# STM32F030.net
KiCad netlist of a schematic drawn in Altium Designer
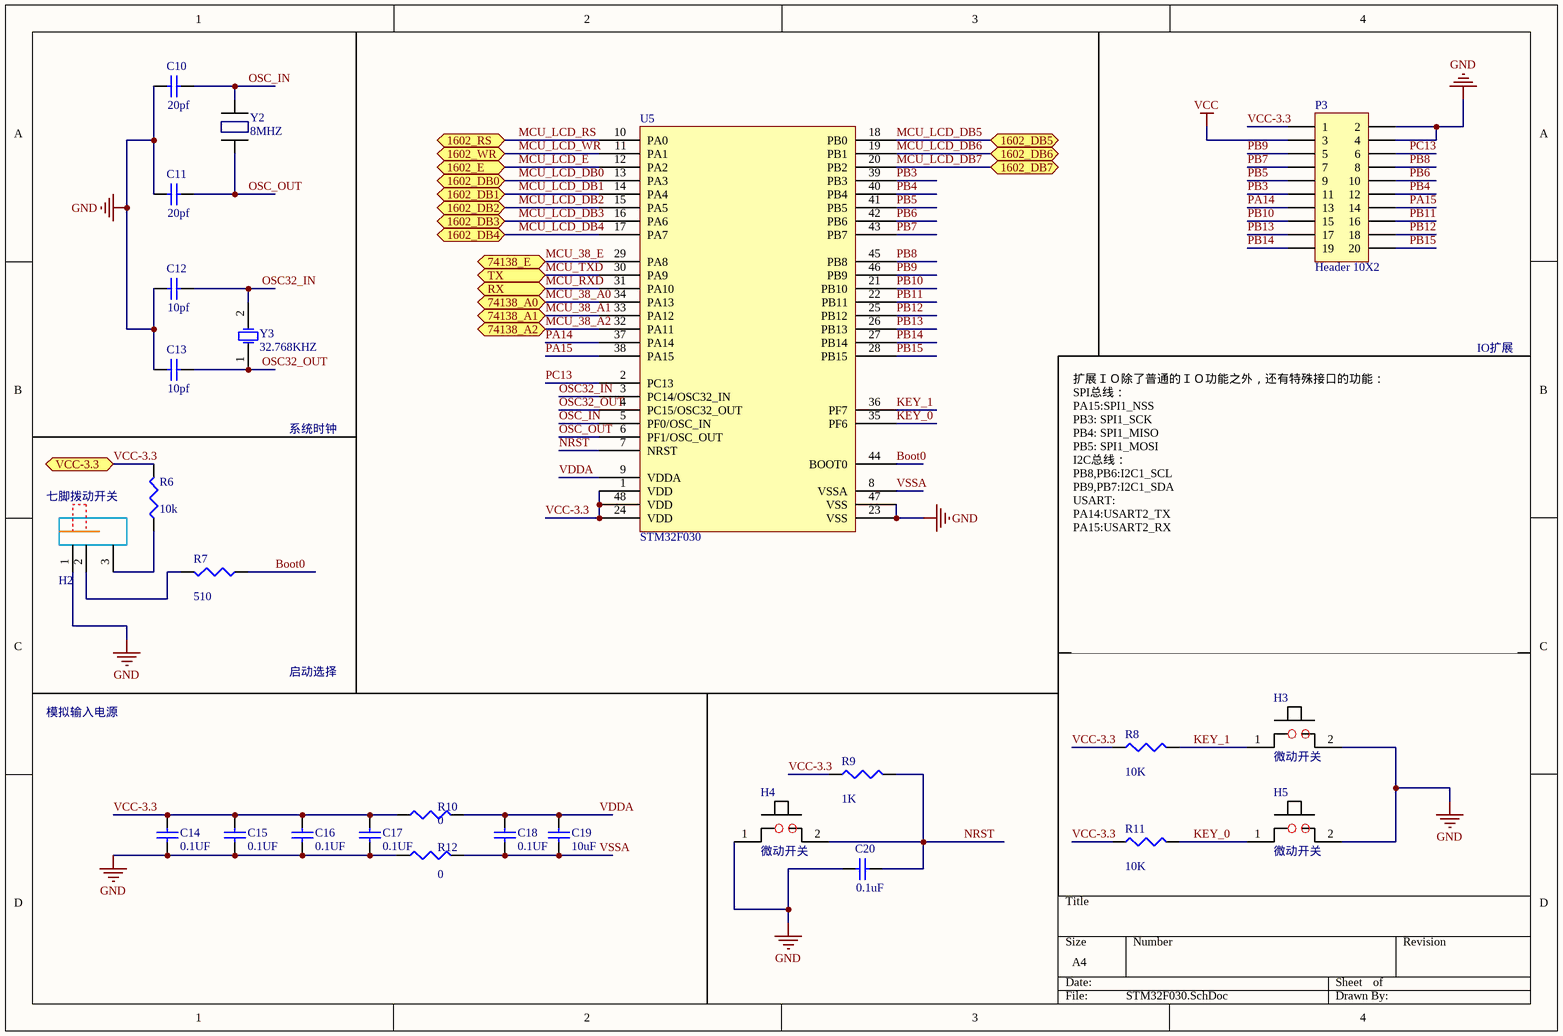
[diagram p0: STM32F030.SchDoc]

(export (version "E")
  (design (tool "Eeschema 10.0.6"))
  (components
    (comp (ref "C10")
      (value "20pf")
      (footprint "C1206")
      (description "Capacitor (Semiconductor SIM Model)")
      (fields (field (name "Comment") "Cap Semi") (field (name "PUBLISHER") "Altium Limited"))
      (libsource (lib "Miscellaneous Devices") (part "Cap Semi"))
    )
    (comp (ref "C11")
      (value "20pf")
      (footprint "C1206")
      (description "Capacitor (Semiconductor SIM Model)")
      (fields (field (name "Comment") "Cap Semi") (field (name "PUBLISHER") "Altium Limited"))
      (libsource (lib "Miscellaneous Devices") (part "Cap Semi"))
    )
    (comp (ref "C12")
      (value "10pf")
      (footprint "C1206")
      (description "Capacitor (Semiconductor SIM Model)")
      (fields (field (name "Comment") "Cap Semi") (field (name "PUBLISHER") "Altium Limited"))
      (libsource (lib "Miscellaneous Devices") (part "Cap Semi"))
    )
    (comp (ref "C13")
      (value "10pf")
      (footprint "C1206")
      (description "Capacitor (Semiconductor SIM Model)")
      (fields (field (name "Comment") "Cap Semi") (field (name "PUBLISHER") "Altium Limited"))
      (libsource (lib "Miscellaneous Devices") (part "Cap Semi"))
    )
    (comp (ref "C14")
      (value "0.1UF")
      (footprint "C1206")
      (description "Capacitor (Semiconductor SIM Model)")
      (fields (field (name "Comment") "Cap Semi") (field (name "PUBLISHER") "Altium Limited"))
      (libsource (lib "Miscellaneous Devices") (part "Cap Semi"))
    )
    (comp (ref "C15")
      (value "0.1UF")
      (footprint "C1206")
      (description "Capacitor (Semiconductor SIM Model)")
      (fields (field (name "Comment") "Cap Semi") (field (name "PUBLISHER") "Altium Limited"))
      (libsource (lib "Miscellaneous Devices") (part "Cap Semi"))
    )
    (comp (ref "C16")
      (value "0.1UF")
      (footprint "C1206")
      (description "Capacitor (Semiconductor SIM Model)")
      (fields (field (name "Comment") "Cap Semi") (field (name "PUBLISHER") "Altium Limited"))
      (libsource (lib "Miscellaneous Devices") (part "Cap Semi"))
    )
    (comp (ref "C17")
      (value "0.1UF")
      (footprint "C1206")
      (description "Capacitor (Semiconductor SIM Model)")
      (fields (field (name "Comment") "Cap Semi") (field (name "PUBLISHER") "Altium Limited"))
      (libsource (lib "Miscellaneous Devices") (part "Cap Semi"))
    )
    (comp (ref "C18")
      (value "0.1UF")
      (footprint "C1206")
      (description "Capacitor (Semiconductor SIM Model)")
      (fields (field (name "Comment") "Cap Semi") (field (name "PUBLISHER") "Altium Limited"))
      (libsource (lib "Miscellaneous Devices") (part "Cap Semi"))
    )
    (comp (ref "C19")
      (value "10uF")
      (footprint "C1206")
      (description "Capacitor (Semiconductor SIM Model)")
      (fields (field (name "Comment") "Cap Semi") (field (name "PUBLISHER") "Altium Limited"))
      (libsource (lib "Miscellaneous Devices") (part "Cap Semi"))
    )
    (comp (ref "C20")
      (value "0.1uF")
      (footprint "C1206")
      (description "Capacitor (Semiconductor SIM Model)")
      (fields (field (name "Comment") "Cap Semi") (field (name "PUBLISHER") "Altium Limited"))
      (libsource (lib "Miscellaneous Devices") (part "Cap Semi"))
    )
    (comp (ref "H2")
      (value "七脚拨动开关")
      (footprint "七脚拨动开关")
      (description "H?")
      (libsource (lib "KindSword") (part "七脚拨动开关"))
    )
    (comp (ref "H3")
      (value "微动开关")
      (footprint "微动开关")
      (description "H?")
      (libsource (lib "KindSword") (part "微动开关"))
    )
    (comp (ref "H4")
      (value "微动开关")
      (footprint "微动开关")
      (description "H?")
      (libsource (lib "KindSword") (part "微动开关"))
    )
    (comp (ref "H5")
      (value "微动开关")
      (footprint "微动开关")
      (description "H?")
      (libsource (lib "KindSword") (part "微动开关"))
    )
    (comp (ref "P3")
      (value "Header 10X2")
      (footprint "HDR2X10")
      (description "Header, 10-Pin, Dual row")
      (fields (field (name "PUBLISHER") "Altium Limited"))
      (libsource (lib "Miscellaneous Connectors") (part "Header 10X2"))
    )
    (comp (ref "R6")
      (value "10k")
      (footprint "14-1210")
      (description "Resistor")
      (fields (field (name "Comment") "Res3") (field (name "PUBLISHER") "Altium Limited"))
      (libsource (lib "Miscellaneous Devices") (part "Res3"))
    )
    (comp (ref "R7")
      (value "510")
      (footprint "14-1210")
      (description "Resistor")
      (fields (field (name "Comment") "Res3") (field (name "PUBLISHER") "Altium Limited"))
      (libsource (lib "Miscellaneous Devices") (part "Res3"))
    )
    (comp (ref "R8")
      (value "10K")
      (footprint "14-1210")
      (description "Resistor")
      (fields (field (name "Comment") "Res3") (field (name "PUBLISHER") "Altium Limited"))
      (libsource (lib "Miscellaneous Devices") (part "Res3"))
    )
    (comp (ref "R9")
      (value "1K")
      (footprint "14-1210")
      (description "Resistor")
      (fields (field (name "Comment") "Res3") (field (name "PUBLISHER") "Altium Limited"))
      (libsource (lib "Miscellaneous Devices") (part "Res3"))
    )
    (comp (ref "R10")
      (value "0")
      (footprint "14-1210")
      (description "Resistor")
      (fields (field (name "Comment") "Res3") (field (name "PUBLISHER") "Altium Limited"))
      (libsource (lib "Miscellaneous Devices") (part "Res3"))
    )
    (comp (ref "R11")
      (value "10K")
      (footprint "14-1210")
      (description "Resistor")
      (fields (field (name "Comment") "Res3") (field (name "PUBLISHER") "Altium Limited"))
      (libsource (lib "Miscellaneous Devices") (part "Res3"))
    )
    (comp (ref "R12")
      (value "0")
      (footprint "14-1210")
      (description "Resistor")
      (fields (field (name "Comment") "Res3") (field (name "PUBLISHER") "Altium Limited"))
      (libsource (lib "Miscellaneous Devices") (part "Res3"))
    )
    (comp (ref "U5")
      (value "STM32F030")
      (footprint "TSQFP50P900X900X160-48N")
      (description "U?")
      (libsource (lib "KindSword") (part "STM32F030C8T6"))
    )
    (comp (ref "Y2")
      (value "8MHZ")
      (footprint "晶振")
      (description "Y?")
      (libsource (lib "KindSword") (part "晶振"))
    )
    (comp (ref "Y3")
      (value "32.768KHZ")
      (footprint "R38")
      (description "Crystal Oscillator")
      (fields (field (name "PUBLISHER") "Altium Limited"))
      (libsource (lib "Miscellaneous Devices") (part "XTAL"))
    )
  )
  (nets
    (net (code "1") (name "/Boot0") (class "Default")
      (node (ref "R7") (pin "1") (pinfunction "1_1") (pintype "passive"))
      (node (ref "U5") (pin "44") (pinfunction "BOOT0_44") (pintype "passive"))
    )
    (net (code "2") (name "/KEY_0") (class "Default")
      (node (ref "H5") (pin "1") (pinfunction "104_1") (pintype "passive"))
      (node (ref "R11") (pin "2") (pinfunction "2_2") (pintype "passive"))
      (node (ref "U5") (pin "35") (pinfunction "PF6_35") (pintype "passive"))
    )
    (net (code "3") (name "/KEY_1") (class "Default")
      (node (ref "H3") (pin "1") (pinfunction "104_1") (pintype "passive"))
      (node (ref "R8") (pin "2") (pinfunction "2_2") (pintype "passive"))
      (node (ref "U5") (pin "36") (pinfunction "PF7_36") (pintype "passive"))
    )
    (net (code "4") (name "/MCU_38_A0") (class "Default")
      (node (ref "U5") (pin "34") (pinfunction "PA13_34") (pintype "passive"))
    )
    (net (code "5") (name "/MCU_38_A1") (class "Default")
      (node (ref "U5") (pin "33") (pinfunction "PA12_33") (pintype "passive"))
    )
    (net (code "6") (name "/MCU_38_A2") (class "Default")
      (node (ref "U5") (pin "32") (pinfunction "PA11_32") (pintype "passive"))
    )
    (net (code "7") (name "/MCU_38_E") (class "Default")
      (node (ref "U5") (pin "29") (pinfunction "PA8_29") (pintype "passive"))
    )
    (net (code "8") (name "/MCU_LCD_DB0") (class "Default")
      (node (ref "U5") (pin "13") (pinfunction "PA3_13") (pintype "passive"))
    )
    (net (code "9") (name "/MCU_LCD_DB1") (class "Default")
      (node (ref "U5") (pin "14") (pinfunction "PA4_14") (pintype "passive"))
    )
    (net (code "10") (name "/MCU_LCD_DB2") (class "Default")
      (node (ref "U5") (pin "15") (pinfunction "PA5_15") (pintype "passive"))
    )
    (net (code "11") (name "/MCU_LCD_DB3") (class "Default")
      (node (ref "U5") (pin "16") (pinfunction "PA6_16") (pintype "passive"))
    )
    (net (code "12") (name "/MCU_LCD_DB4") (class "Default")
      (node (ref "U5") (pin "17") (pinfunction "PA7_17") (pintype "passive"))
    )
    (net (code "13") (name "/MCU_LCD_DB5") (class "Default")
      (node (ref "U5") (pin "18") (pinfunction "PB0_18") (pintype "passive"))
    )
    (net (code "14") (name "/MCU_LCD_DB6") (class "Default")
      (node (ref "U5") (pin "19") (pinfunction "PB1_19") (pintype "passive"))
    )
    (net (code "15") (name "/MCU_LCD_DB7") (class "Default")
      (node (ref "U5") (pin "20") (pinfunction "PB2_20") (pintype "passive"))
    )
    (net (code "16") (name "/MCU_LCD_E") (class "Default")
      (node (ref "U5") (pin "12") (pinfunction "PA2_12") (pintype "passive"))
    )
    (net (code "17") (name "/MCU_LCD_RS") (class "Default")
      (node (ref "U5") (pin "10") (pinfunction "PA0_10") (pintype "passive"))
    )
    (net (code "18") (name "/MCU_LCD_WR") (class "Default")
      (node (ref "U5") (pin "11") (pinfunction "PA1_11") (pintype "passive"))
    )
    (net (code "19") (name "/MCU_RXD") (class "Default")
      (node (ref "U5") (pin "31") (pinfunction "PA10_31") (pintype "passive"))
    )
    (net (code "20") (name "/MCU_TXD") (class "Default")
      (node (ref "U5") (pin "30") (pinfunction "PA9_30") (pintype "passive"))
    )
    (net (code "21") (name "/NRST") (class "Default")
      (node (ref "C20") (pin "2") (pinfunction "2_2") (pintype "passive"))
      (node (ref "H4") (pin "2") (pinfunction "105_2") (pintype "passive"))
      (node (ref "R9") (pin "2") (pinfunction "2_2") (pintype "passive"))
      (node (ref "U5") (pin "7") (pinfunction "NRST_7") (pintype "passive"))
    )
    (net (code "22") (name "/OSC32_IN") (class "Default")
      (node (ref "C12") (pin "2") (pinfunction "2_2") (pintype "passive"))
      (node (ref "U5") (pin "3") (pinfunction "PC14/OSC32_IN_3") (pintype "passive"))
      (node (ref "Y3") (pin "2") (pinfunction "OSC2_2") (pintype "passive"))
    )
    (net (code "23") (name "/OSC32_OUT") (class "Default")
      (node (ref "C13") (pin "2") (pinfunction "2_2") (pintype "passive"))
      (node (ref "U5") (pin "4") (pinfunction "PC15/OSC32_OUT_4") (pintype "passive"))
      (node (ref "Y3") (pin "1") (pinfunction "OSC1_1") (pintype "passive"))
    )
    (net (code "24") (name "/OSC_IN") (class "Default")
      (node (ref "C10") (pin "2") (pinfunction "2_2") (pintype "passive"))
      (node (ref "U5") (pin "5") (pinfunction "PF0/OSC_IN_5") (pintype "passive"))
      (node (ref "Y2") (pin "2") (pintype "passive"))
    )
    (net (code "25") (name "/OSC_OUT") (class "Default")
      (node (ref "C11") (pin "2") (pinfunction "2_2") (pintype "passive"))
      (node (ref "U5") (pin "6") (pinfunction "PF1/OSC_OUT_6") (pintype "passive"))
      (node (ref "Y2") (pin "1") (pintype "passive"))
    )
    (net (code "26") (name "/PA14") (class "Default")
      (node (ref "P3") (pin "13") (pinfunction "13_13") (pintype "passive"))
      (node (ref "U5") (pin "37") (pinfunction "PA14_37") (pintype "passive"))
    )
    (net (code "27") (name "/PA15") (class "Default")
      (node (ref "P3") (pin "14") (pinfunction "14_14") (pintype "passive"))
      (node (ref "U5") (pin "38") (pinfunction "PA15_38") (pintype "passive"))
    )
    (net (code "28") (name "/PB3") (class "Default")
      (node (ref "P3") (pin "11") (pinfunction "11_11") (pintype "passive"))
      (node (ref "U5") (pin "39") (pinfunction "PB3_39") (pintype "passive"))
    )
    (net (code "29") (name "/PB4") (class "Default")
      (node (ref "P3") (pin "12") (pinfunction "12_12") (pintype "passive"))
      (node (ref "U5") (pin "40") (pinfunction "PB4_40") (pintype "passive"))
    )
    (net (code "30") (name "/PB5") (class "Default")
      (node (ref "P3") (pin "9") (pinfunction "9_9") (pintype "passive"))
      (node (ref "U5") (pin "41") (pinfunction "PB5_41") (pintype "passive"))
    )
    (net (code "31") (name "/PB6") (class "Default")
      (node (ref "P3") (pin "10") (pinfunction "10_10") (pintype "passive"))
      (node (ref "U5") (pin "42") (pinfunction "PB6_42") (pintype "passive"))
    )
    (net (code "32") (name "/PB7") (class "Default")
      (node (ref "P3") (pin "7") (pinfunction "7_7") (pintype "passive"))
      (node (ref "U5") (pin "43") (pinfunction "PB7_43") (pintype "passive"))
    )
    (net (code "33") (name "/PB8") (class "Default")
      (node (ref "P3") (pin "8") (pinfunction "8_8") (pintype "passive"))
      (node (ref "U5") (pin "45") (pinfunction "PB8_45") (pintype "passive"))
    )
    (net (code "34") (name "/PB9") (class "Default")
      (node (ref "P3") (pin "5") (pinfunction "5_5") (pintype "passive"))
      (node (ref "U5") (pin "46") (pinfunction "PB9_46") (pintype "passive"))
    )
    (net (code "35") (name "/PB10") (class "Default")
      (node (ref "P3") (pin "15") (pinfunction "15_15") (pintype "passive"))
      (node (ref "U5") (pin "21") (pinfunction "PB10_21") (pintype "passive"))
    )
    (net (code "36") (name "/PB11") (class "Default")
      (node (ref "P3") (pin "16") (pinfunction "16_16") (pintype "passive"))
      (node (ref "U5") (pin "22") (pinfunction "PB11_22") (pintype "passive"))
    )
    (net (code "37") (name "/PB12") (class "Default")
      (node (ref "P3") (pin "18") (pinfunction "18_18") (pintype "passive"))
      (node (ref "U5") (pin "25") (pinfunction "PB12_25") (pintype "passive"))
    )
    (net (code "38") (name "/PB13") (class "Default")
      (node (ref "P3") (pin "17") (pinfunction "17_17") (pintype "passive"))
      (node (ref "U5") (pin "26") (pinfunction "PB13_26") (pintype "passive"))
    )
    (net (code "39") (name "/PB14") (class "Default")
      (node (ref "P3") (pin "19") (pinfunction "19_19") (pintype "passive"))
      (node (ref "U5") (pin "27") (pinfunction "PB14_27") (pintype "passive"))
    )
    (net (code "40") (name "/PB15") (class "Default")
      (node (ref "P3") (pin "20") (pinfunction "20_20") (pintype "passive"))
      (node (ref "U5") (pin "28") (pinfunction "PB15_28") (pintype "passive"))
    )
    (net (code "41") (name "/PC13") (class "Default")
      (node (ref "P3") (pin "6") (pinfunction "6_6") (pintype "passive"))
      (node (ref "U5") (pin "2") (pinfunction "PC13_2") (pintype "passive"))
    )
    (net (code "42") (name "/VCC-3.3") (class "Default")
      (node (ref "C14") (pin "2") (pinfunction "2_2") (pintype "passive"))
      (node (ref "C15") (pin "2") (pinfunction "2_2") (pintype "passive"))
      (node (ref "C16") (pin "2") (pinfunction "2_2") (pintype "passive"))
      (node (ref "C17") (pin "2") (pinfunction "2_2") (pintype "passive"))
      (node (ref "P3") (pin "1") (pinfunction "1_1") (pintype "passive"))
      (node (ref "R10") (pin "1") (pinfunction "1_1") (pintype "passive"))
      (node (ref "R11") (pin "1") (pinfunction "1_1") (pintype "passive"))
      (node (ref "R6") (pin "2") (pinfunction "2_2") (pintype "passive"))
      (node (ref "R8") (pin "1") (pinfunction "1_1") (pintype "passive"))
      (node (ref "R9") (pin "1") (pinfunction "1_1") (pintype "passive"))
      (node (ref "U5") (pin "1") (pinfunction "VDD_1") (pintype "passive"))
      (node (ref "U5") (pin "24") (pinfunction "VDD_24") (pintype "passive"))
      (node (ref "U5") (pin "48") (pinfunction "VDD_48") (pintype "passive"))
    )
    (net (code "43") (name "/VDDA") (class "Default")
      (node (ref "C18") (pin "2") (pinfunction "2_2") (pintype "passive"))
      (node (ref "C19") (pin "2") (pinfunction "2_2") (pintype "passive"))
      (node (ref "R10") (pin "2") (pinfunction "2_2") (pintype "passive"))
      (node (ref "U5") (pin "9") (pinfunction "VDDA_9") (pintype "passive"))
    )
    (net (code "44") (name "/VSSA") (class "Default")
      (node (ref "C18") (pin "1") (pinfunction "1_1") (pintype "passive"))
      (node (ref "C19") (pin "1") (pinfunction "1_1") (pintype "passive"))
      (node (ref "R12") (pin "2") (pinfunction "2_2") (pintype "passive"))
      (node (ref "U5") (pin "8") (pinfunction "VSSA_8") (pintype "passive"))
    )
    (net (code "45") (name "GND") (class "Default")
      (node (ref "C10") (pin "1") (pinfunction "1_1") (pintype "passive"))
      (node (ref "C11") (pin "1") (pinfunction "1_1") (pintype "passive"))
      (node (ref "C12") (pin "1") (pinfunction "1_1") (pintype "passive"))
      (node (ref "C13") (pin "1") (pinfunction "1_1") (pintype "passive"))
      (node (ref "C14") (pin "1") (pinfunction "1_1") (pintype "passive"))
      (node (ref "C15") (pin "1") (pinfunction "1_1") (pintype "passive"))
      (node (ref "C16") (pin "1") (pinfunction "1_1") (pintype "passive"))
      (node (ref "C17") (pin "1") (pinfunction "1_1") (pintype "passive"))
      (node (ref "C20") (pin "1") (pinfunction "1_1") (pintype "passive"))
      (node (ref "H2") (pin "1") (pinfunction "3_1") (pintype "passive"))
      (node (ref "H3") (pin "2") (pinfunction "105_2") (pintype "passive"))
      (node (ref "H4") (pin "1") (pinfunction "104_1") (pintype "passive"))
      (node (ref "H5") (pin "2") (pinfunction "105_2") (pintype "passive"))
      (node (ref "P3") (pin "2") (pinfunction "2_2") (pintype "passive"))
      (node (ref "P3") (pin "4") (pinfunction "4_4") (pintype "passive"))
      (node (ref "R12") (pin "1") (pinfunction "1_1") (pintype "passive"))
      (node (ref "U5") (pin "23") (pinfunction "VSS_23") (pintype "passive"))
      (node (ref "U5") (pin "47") (pinfunction "VSS_47") (pintype "passive"))
    )
    (net (code "46") (name "Net-(H2-4)") (class "Default")
      (node (ref "H2") (pin "2") (pinfunction "4_2") (pintype "passive"))
      (node (ref "R7") (pin "2") (pinfunction "2_2") (pintype "passive"))
    )
    (net (code "47") (name "Net-(H2-5)") (class "Default")
      (node (ref "H2") (pin "3") (pinfunction "5_3") (pintype "passive"))
      (node (ref "R6") (pin "1") (pinfunction "1_1") (pintype "passive"))
    )
    (net (code "48") (name "VCC") (class "Default")
      (node (ref "P3") (pin "3") (pinfunction "3_3") (pintype "passive"))
    )
  )
)
